# LED_12T-V1_1.net
KiCad netlist of a schematic drawn in Altium Designer
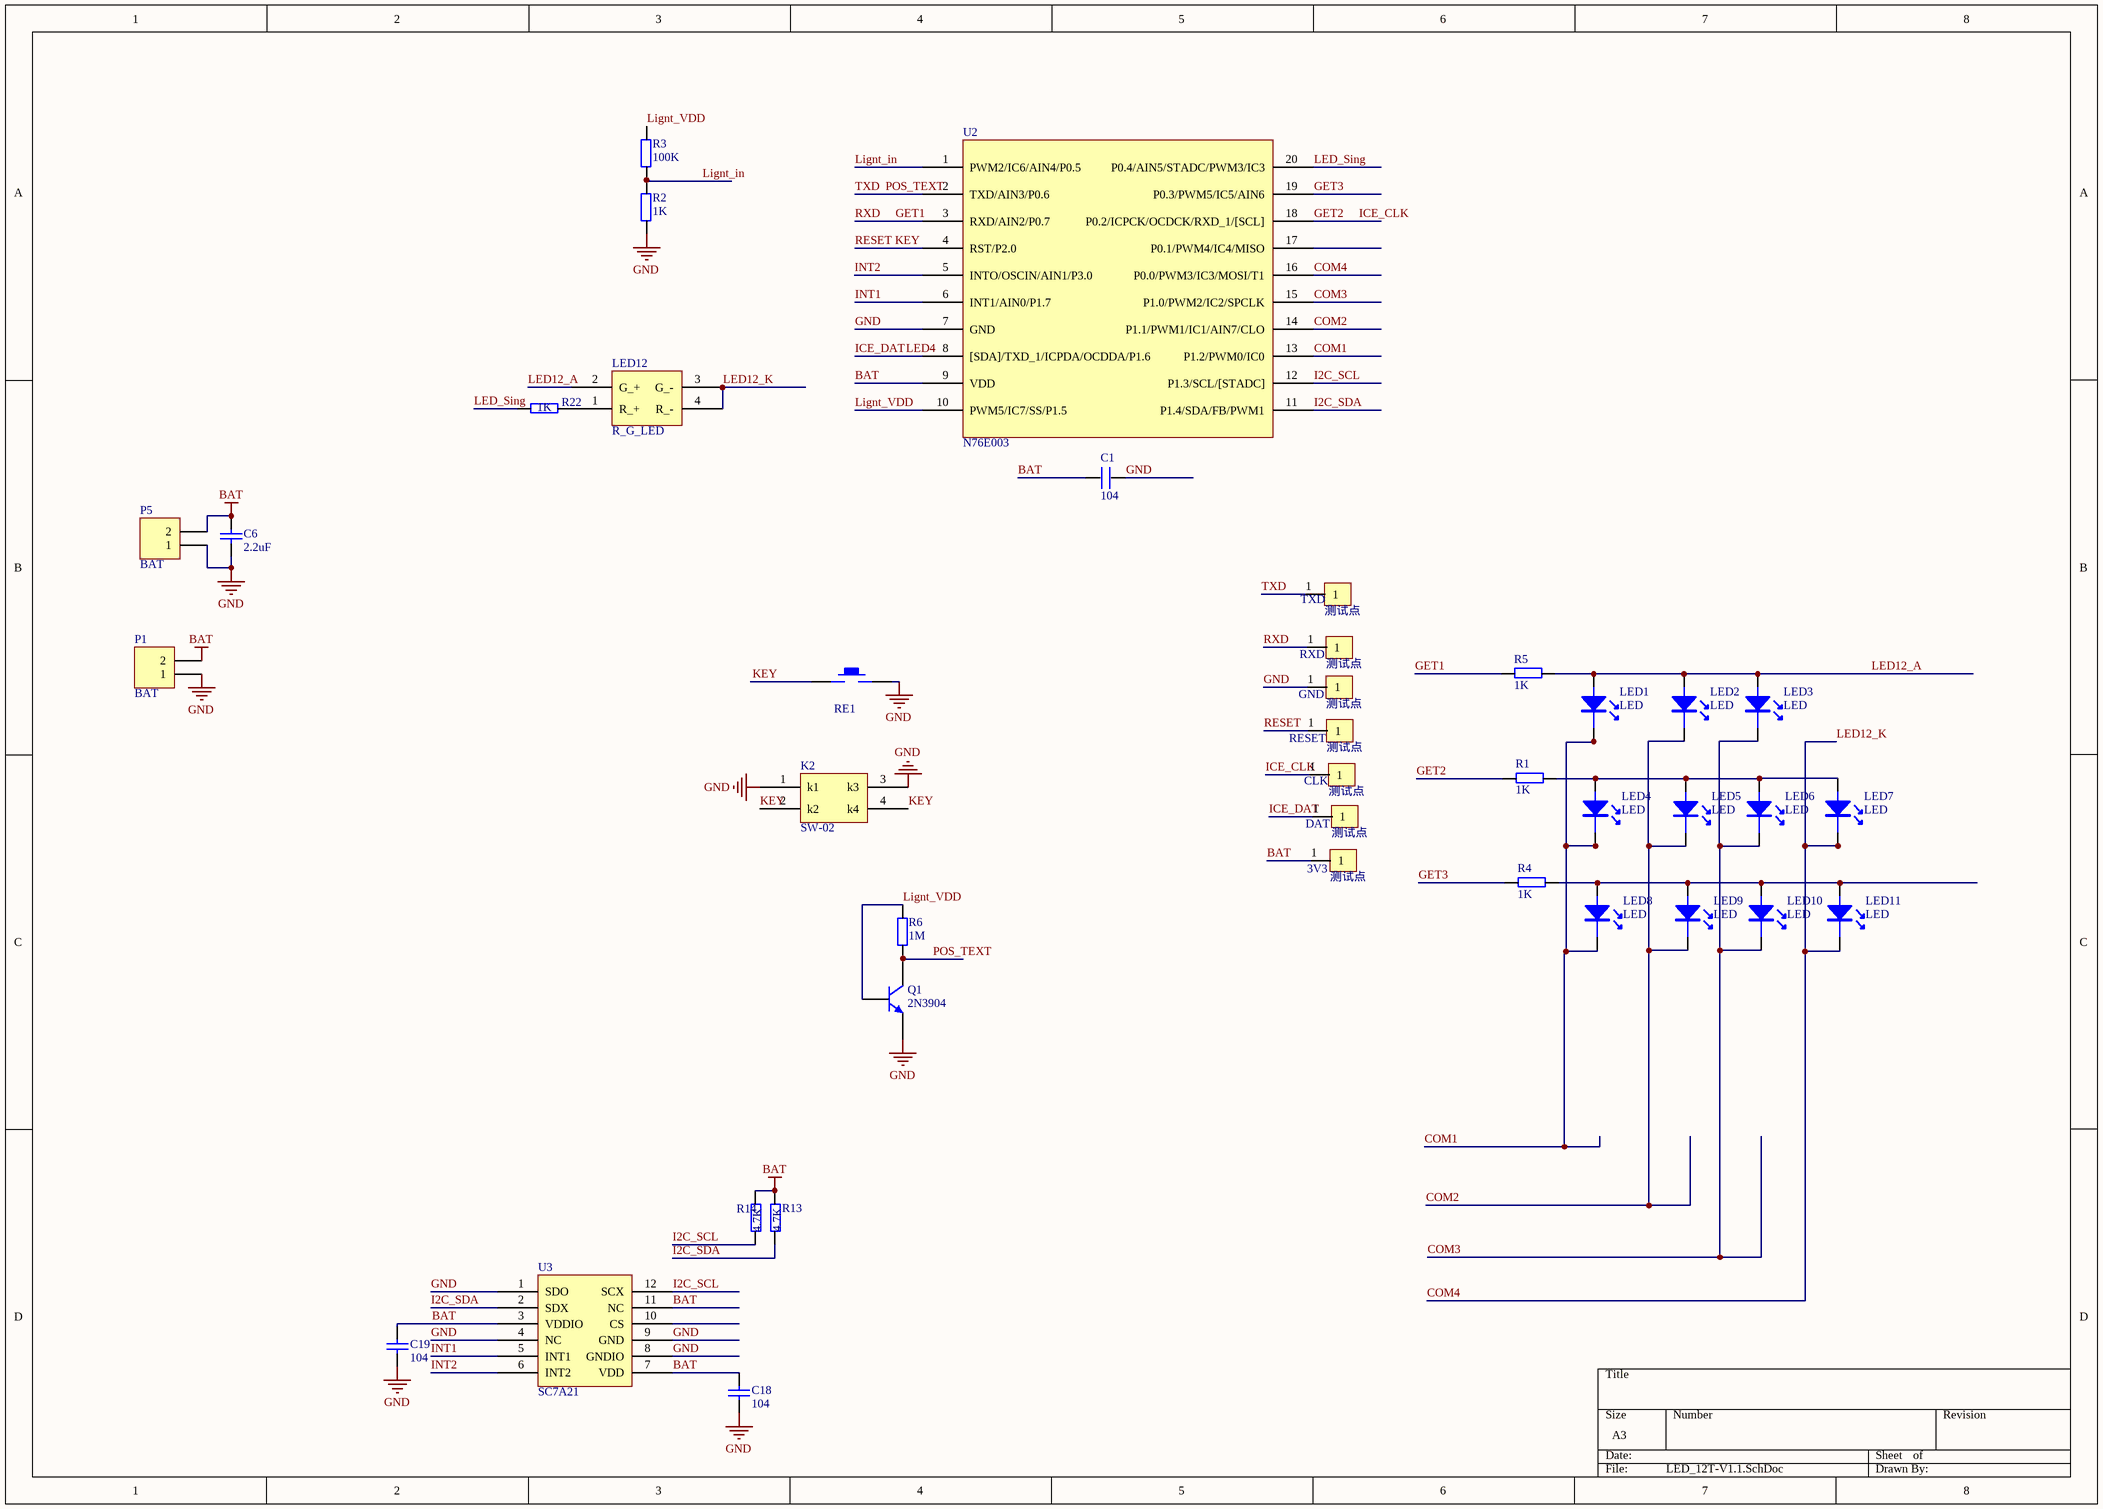
[diagram p0: LED_12T-V1.1.SchDoc]

(export (version "E")
  (design (tool "Eeschema 10.0.6"))
  (components
    (comp (ref "3V3") (value "测试点") (footprint "测试点") (libsource (lib "元件") (part "测试点")))
    (comp (ref "C1") (value "104") (footprint "0603P") (libsource (lib "3.5TFTLCD封装库") (part "C")))
    (comp (ref "C6")
      (value "2.2uF")
      (footprint "0603_C")
      (description "Capacitor")
      (fields (field (name "PUBLISHER") "Altium Limited"))
      (libsource (lib "Miscellaneous Devices") (part "Cap"))
    )
    (comp (ref "C18")
      (value "104")
      (footprint "0402_C")
      (description "Capacitor")
      (fields (field (name "PUBLISHER") "Altium Limited"))
      (libsource (lib "Miscellaneous Devices") (part "Cap"))
    )
    (comp (ref "C19")
      (value "104")
      (footprint "0402_C")
      (description "Capacitor")
      (fields (field (name "PUBLISHER") "Altium Limited"))
      (libsource (lib "Miscellaneous Devices") (part "Cap"))
    )
    (comp (ref "CLK") (value "测试点") (footprint "测试点") (libsource (lib "元件") (part "测试点")))
    (comp (ref "DAT") (value "测试点") (footprint "测试点") (libsource (lib "元件") (part "测试点")))
    (comp (ref "GND") (value "测试点") (footprint "测试点") (libsource (lib "元件") (part "测试点")))
    (comp (ref "K2") (value "SW-02") (footprint "四向滚珠开关") (libsource (lib "元件") (part "SW-02")))
    (comp (ref "LED1") (value "LED") (footprint "0402_LED") (libsource (lib "*") (part "LED")))
    (comp (ref "LED2") (value "LED") (footprint "0402_LED") (libsource (lib "*") (part "LED")))
    (comp (ref "LED3") (value "LED") (footprint "0402_LED") (libsource (lib "*") (part "LED")))
    (comp (ref "LED4") (value "LED") (footprint "0402_LED") (libsource (lib "*") (part "LED")))
    (comp (ref "LED5") (value "LED") (footprint "0402_LED") (libsource (lib "*") (part "LED")))
    (comp (ref "LED6") (value "LED") (footprint "0402_LED") (libsource (lib "*") (part "LED")))
    (comp (ref "LED7") (value "LED") (footprint "0402_LED") (libsource (lib "*") (part "LED")))
    (comp (ref "LED8") (value "LED") (footprint "0402_LED") (libsource (lib "*") (part "LED")))
    (comp (ref "LED9") (value "LED") (footprint "0402_LED") (libsource (lib "*") (part "LED")))
    (comp (ref "LED10") (value "LED") (footprint "0402_LED") (libsource (lib "*") (part "LED")))
    (comp (ref "LED11") (value "LED") (footprint "0402_LED") (libsource (lib "*") (part "LED")))
    (comp (ref "LED12") (value "R_G_LED") (footprint "0603_R_G_LED") (libsource (lib "元件") (part "R_G_LED")))
    (comp (ref "P1")
      (value "BAT")
      (footprint "SH1.0-2P")
      (description "Header, 2-Pin")
      (fields (field (name "PUBLISHER") "Altium Limited"))
      (libsource (lib "Miscellaneous Connectors") (part "Header 2"))
    )
    (comp (ref "P5")
      (value "BAT")
      (footprint "CR2450")
      (description "Header, 2-Pin")
      (fields (field (name "PUBLISHER") "Altium Limited"))
      (libsource (lib "Miscellaneous Connectors") (part "Header 2"))
    )
    (comp (ref "Q1")
      (value "2N3904")
      (footprint "SOT-23")
      (description "NPN General Purpose Amplifier")
      (fields (field (name "PUBLISHER") "Altium Limited"))
      (libsource (lib "Miscellaneous Devices") (part "2N3904"))
    )
    (comp (ref "R1")
      (value "1K")
      (footprint "自画库1:0402_R")
      (libsource (lib "Explorer STM32F407封装库") (part "R"))
    )
    (comp (ref "R2")
      (value "1K")
      (footprint "自画库1:0603_R")
      (libsource (lib "Explorer STM32F407封装库") (part "R"))
    )
    (comp (ref "R3")
      (value "100K")
      (footprint "自画库1:0402_R")
      (libsource (lib "Explorer STM32F407封装库") (part "R"))
    )
    (comp (ref "R4")
      (value "1K")
      (footprint "自画库1:0402_R")
      (libsource (lib "Explorer STM32F407封装库") (part "R"))
    )
    (comp (ref "R5")
      (value "1K")
      (footprint "自画库1:0402_R")
      (libsource (lib "Explorer STM32F407封装库") (part "R"))
    )
    (comp (ref "R6")
      (value "1M")
      (footprint "自画库1:0402_R")
      (libsource (lib "Explorer STM32F407封装库") (part "R"))
    )
    (comp (ref "R13")
      (value "4.7K")
      (footprint "自画库1:0402_R")
      (libsource (lib "Explorer STM32F407封装库") (part "R"))
    )
    (comp (ref "R14")
      (value "4.7K")
      (footprint "自画库1:0402_R")
      (libsource (lib "Explorer STM32F407封装库") (part "R"))
    )
    (comp (ref "R22")
      (value "1K")
      (footprint "自画库1:0402_R")
      (libsource (lib "Explorer STM32F407封装库") (part "R"))
    )
    (comp (ref "RE1")
      (value "KEY_M")
      (footprint "滚珠开关12*3.6")
      (libsource (lib "Explorer STM32F407封装库") (part "KEY_M"))
    )
    (comp (ref "RESET") (value "测试点") (footprint "测试点") (libsource (lib "元件") (part "测试点")))
    (comp (ref "RXD") (value "测试点") (footprint "测试点") (libsource (lib "元件") (part "测试点")))
    (comp (ref "TXD") (value "测试点") (footprint "测试点") (libsource (lib "元件") (part "测试点")))
    (comp (ref "U2") (value "N76E003") (footprint "STSOP20") (libsource (lib "元件") (part "N76E003")))
    (comp (ref "U3") (value "SC7A21") (footprint "自画库1:LGA-12-2*2*1") (libsource (lib "元件") (part "SC7A21")))
  )
  (nets
    (net (code "1") (name "/COM1") (class "Default")
      (node (ref "LED1") (pin "2") (pinfunction "K_2") (pintype "passive"))
      (node (ref "LED4") (pin "2") (pinfunction "K_2") (pintype "passive"))
      (node (ref "LED8") (pin "2") (pinfunction "K_2") (pintype "passive"))
      (node (ref "U2") (pin "13") (pinfunction "P1.2/PWM0/IC0_13") (pintype "passive"))
    )
    (net (code "2") (name "/COM2") (class "Default")
      (node (ref "LED2") (pin "2") (pinfunction "K_2") (pintype "passive"))
      (node (ref "LED5") (pin "2") (pinfunction "K_2") (pintype "passive"))
      (node (ref "LED9") (pin "2") (pinfunction "K_2") (pintype "passive"))
      (node (ref "U2") (pin "14") (pinfunction "P1.1/PWM1/IC1/AIN7/CLO_14") (pintype "passive"))
    )
    (net (code "3") (name "/COM3") (class "Default")
      (node (ref "LED10") (pin "2") (pinfunction "K_2") (pintype "passive"))
      (node (ref "LED3") (pin "2") (pinfunction "K_2") (pintype "passive"))
      (node (ref "LED6") (pin "2") (pinfunction "K_2") (pintype "passive"))
      (node (ref "U2") (pin "15") (pinfunction "P1.0/PWM2/IC2/SPCLK_15") (pintype "passive"))
    )
    (net (code "4") (name "/COM4") (class "Default")
      (node (ref "LED11") (pin "2") (pinfunction "K_2") (pintype "passive"))
      (node (ref "LED12") (pin "3") (pinfunction "G_-_3") (pintype "passive"))
      (node (ref "LED12") (pin "4") (pinfunction "R_-_4") (pintype "passive"))
      (node (ref "LED7") (pin "2") (pinfunction "K_2") (pintype "passive"))
      (node (ref "U2") (pin "16") (pinfunction "P0.0/PWM3/IC3/MOSI/T1_16") (pintype "passive"))
    )
    (net (code "5") (name "/GET1") (class "Default")
      (node (ref "R5") (pin "2") (pintype "passive"))
      (node (ref "RXD") (pin "1") (pinfunction "1_1") (pintype "passive"))
      (node (ref "U2") (pin "3") (pinfunction "RXD/AIN2/P0.7_3") (pintype "passive"))
    )
    (net (code "6") (name "/GET2") (class "Default")
      (node (ref "CLK") (pin "1") (pinfunction "1_1") (pintype "passive"))
      (node (ref "R1") (pin "2") (pintype "passive"))
      (node (ref "U2") (pin "18") (pinfunction "P0.2/ICPCK/OCDCK/RXD_1/[SCL]_18") (pintype "passive"))
    )
    (net (code "7") (name "/GET3") (class "Default")
      (node (ref "R4") (pin "2") (pintype "passive"))
      (node (ref "U2") (pin "19") (pinfunction "P0.3/PWM5/IC5/AIN6_19") (pintype "passive"))
    )
    (net (code "8") (name "/I2C_SCL") (class "Default")
      (node (ref "R14") (pin "1") (pintype "passive"))
      (node (ref "U2") (pin "12") (pinfunction "P1.3/SCL/[STADC]_12") (pintype "passive"))
      (node (ref "U3") (pin "12") (pinfunction "SCX_12") (pintype "passive"))
    )
    (net (code "9") (name "/I2C_SDA") (class "Default")
      (node (ref "R13") (pin "1") (pintype "passive"))
      (node (ref "U2") (pin "11") (pinfunction "P1.4/SDA/FB/PWM1_11") (pintype "passive"))
      (node (ref "U3") (pin "2") (pinfunction "SDX_2") (pintype "passive"))
    )
    (net (code "10") (name "/ICE_DAT") (class "Default")
      (node (ref "DAT") (pin "1") (pinfunction "1_1") (pintype "passive"))
      (node (ref "U2") (pin "8") (pinfunction "[SDA]/TXD_1/ICPDA/OCDDA/P1.6_8") (pintype "passive"))
    )
    (net (code "11") (name "/INT1") (class "Default")
      (node (ref "U2") (pin "6") (pinfunction "INT1/AIN0/P1.7_6") (pintype "passive"))
      (node (ref "U3") (pin "5") (pinfunction "INT1_5") (pintype "passive"))
    )
    (net (code "12") (name "/INT2") (class "Default")
      (node (ref "U2") (pin "5") (pinfunction "INTO/OSCIN/AIN1/P3.0_5") (pintype "passive"))
      (node (ref "U3") (pin "6") (pinfunction "INT2_6") (pintype "passive"))
    )
    (net (code "13") (name "/KEY") (class "Default")
      (node (ref "K2") (pin "2") (pinfunction "k2_2") (pintype "passive"))
      (node (ref "K2") (pin "4") (pinfunction "k4_4") (pintype "passive"))
      (node (ref "RE1") (pin "1") (pinfunction "1_1") (pintype "passive"))
      (node (ref "RESET") (pin "1") (pinfunction "1_1") (pintype "passive"))
      (node (ref "U2") (pin "4") (pinfunction "RST/P2.0_4") (pintype "passive"))
    )
    (net (code "14") (name "/LED12_A") (class "Default")
      (node (ref "LED1") (pin "1") (pinfunction "A_1") (pintype "passive"))
      (node (ref "LED12") (pin "2") (pinfunction "G_+_2") (pintype "passive"))
      (node (ref "LED2") (pin "1") (pinfunction "A_1") (pintype "passive"))
      (node (ref "LED3") (pin "1") (pinfunction "A_1") (pintype "passive"))
      (node (ref "R5") (pin "1") (pintype "passive"))
    )
    (net (code "15") (name "/LED_Sing") (class "Default")
      (node (ref "R22") (pin "2") (pintype "passive"))
      (node (ref "U2") (pin "20") (pinfunction "P0.4/AIN5/STADC/PWM3/IC3_20") (pintype "passive"))
    )
    (net (code "16") (name "/Lignt_VDD") (class "Default")
      (node (ref "Q1") (pin "2") (pinfunction "B_2") (pintype "passive"))
      (node (ref "R3") (pin "1") (pintype "passive"))
      (node (ref "R6") (pin "1") (pintype "passive"))
      (node (ref "U2") (pin "10") (pinfunction "PWM5/IC7/SS/P1.5_10") (pintype "passive"))
    )
    (net (code "17") (name "/Lignt_in") (class "Default")
      (node (ref "R2") (pin "1") (pintype "passive"))
      (node (ref "R3") (pin "2") (pintype "passive"))
      (node (ref "U2") (pin "1") (pinfunction "PWM2/IC6/AIN4/P0.5_1") (pintype "passive"))
    )
    (net (code "18") (name "/POS_TEXT") (class "Default")
      (node (ref "Q1") (pin "3") (pinfunction "C_3") (pintype "passive"))
      (node (ref "R6") (pin "2") (pintype "passive"))
      (node (ref "TXD") (pin "1") (pinfunction "1_1") (pintype "passive"))
      (node (ref "U2") (pin "2") (pinfunction "TXD/AIN3/P0.6_2") (pintype "passive"))
    )
    (net (code "19") (name "BAT") (class "Default")
      (node (ref "3V3") (pin "1") (pinfunction "1_1") (pintype "passive"))
      (node (ref "C1") (pin "2") (pintype "passive"))
      (node (ref "C18") (pin "1") (pinfunction "1_1") (pintype "passive"))
      (node (ref "C19") (pin "1") (pinfunction "1_1") (pintype "passive"))
      (node (ref "C6") (pin "2") (pinfunction "2_2") (pintype "passive"))
      (node (ref "P1") (pin "2") (pinfunction "2_2") (pintype "passive"))
      (node (ref "P5") (pin "2") (pinfunction "2_2") (pintype "passive"))
      (node (ref "R13") (pin "2") (pintype "passive"))
      (node (ref "R14") (pin "2") (pintype "passive"))
      (node (ref "U2") (pin "9") (pinfunction "VDD_9") (pintype "passive"))
      (node (ref "U3") (pin "11") (pinfunction "NC_11") (pintype "passive"))
      (node (ref "U3") (pin "3") (pinfunction "VDDIO_3") (pintype "passive"))
      (node (ref "U3") (pin "7") (pinfunction "VDD_7") (pintype "passive"))
    )
    (net (code "20") (name "GND") (class "Default")
      (node (ref "C1") (pin "1") (pintype "passive"))
      (node (ref "C18") (pin "2") (pinfunction "2_2") (pintype "passive"))
      (node (ref "C19") (pin "2") (pinfunction "2_2") (pintype "passive"))
      (node (ref "C6") (pin "1") (pinfunction "1_1") (pintype "passive"))
      (node (ref "GND") (pin "1") (pinfunction "1_1") (pintype "passive"))
      (node (ref "K2") (pin "1") (pinfunction "k1_1") (pintype "passive"))
      (node (ref "K2") (pin "3") (pinfunction "k3_3") (pintype "passive"))
      (node (ref "P1") (pin "1") (pinfunction "1_1") (pintype "passive"))
      (node (ref "P5") (pin "1") (pinfunction "1_1") (pintype "passive"))
      (node (ref "Q1") (pin "1") (pinfunction "E_1") (pintype "passive"))
      (node (ref "R2") (pin "2") (pintype "passive"))
      (node (ref "RE1") (pin "2") (pinfunction "2_2") (pintype "passive"))
      (node (ref "U2") (pin "7") (pinfunction "GND_7") (pintype "passive"))
      (node (ref "U3") (pin "1") (pinfunction "SDO_1") (pintype "passive"))
      (node (ref "U3") (pin "4") (pinfunction "NC_4") (pintype "passive"))
      (node (ref "U3") (pin "8") (pinfunction "GNDIO_8") (pintype "passive"))
      (node (ref "U3") (pin "9") (pinfunction "GND_9") (pintype "passive"))
    )
    (net (code "21") (name "Net-(LED4-A)") (class "Default")
      (node (ref "LED4") (pin "1") (pinfunction "A_1") (pintype "passive"))
      (node (ref "LED5") (pin "1") (pinfunction "A_1") (pintype "passive"))
      (node (ref "LED6") (pin "1") (pinfunction "A_1") (pintype "passive"))
      (node (ref "LED7") (pin "1") (pinfunction "A_1") (pintype "passive"))
      (node (ref "R1") (pin "1") (pintype "passive"))
    )
    (net (code "22") (name "Net-(LED10-A)") (class "Default")
      (node (ref "LED10") (pin "1") (pinfunction "A_1") (pintype "passive"))
      (node (ref "LED11") (pin "1") (pinfunction "A_1") (pintype "passive"))
      (node (ref "LED8") (pin "1") (pinfunction "A_1") (pintype "passive"))
      (node (ref "LED9") (pin "1") (pinfunction "A_1") (pintype "passive"))
      (node (ref "R4") (pin "1") (pintype "passive"))
    )
    (net (code "23") (name "Net-(LED12-R_+)") (class "Default")
      (node (ref "LED12") (pin "1") (pinfunction "R_+_1") (pintype "passive"))
      (node (ref "R22") (pin "1") (pintype "passive"))
    )
    (net (code "24") (name "unconnected-(U2-P0.1{slash}PWM4{slash}IC4{slash}MISO-Pad17)") (class "Default")
      (node (ref "U2") (pin "17") (pinfunction "P0.1/PWM4/IC4/MISO_17") (pintype "passive"))
    )
    (net (code "25") (name "unconnected-(U3-CS-Pad10)") (class "Default")
      (node (ref "U3") (pin "10") (pinfunction "CS_10") (pintype "passive"))
    )
  )
)
